# ccnor_stm32_v24-sync-unified-ss.net
KiCad netlist of a schematic drawn in EAGLE
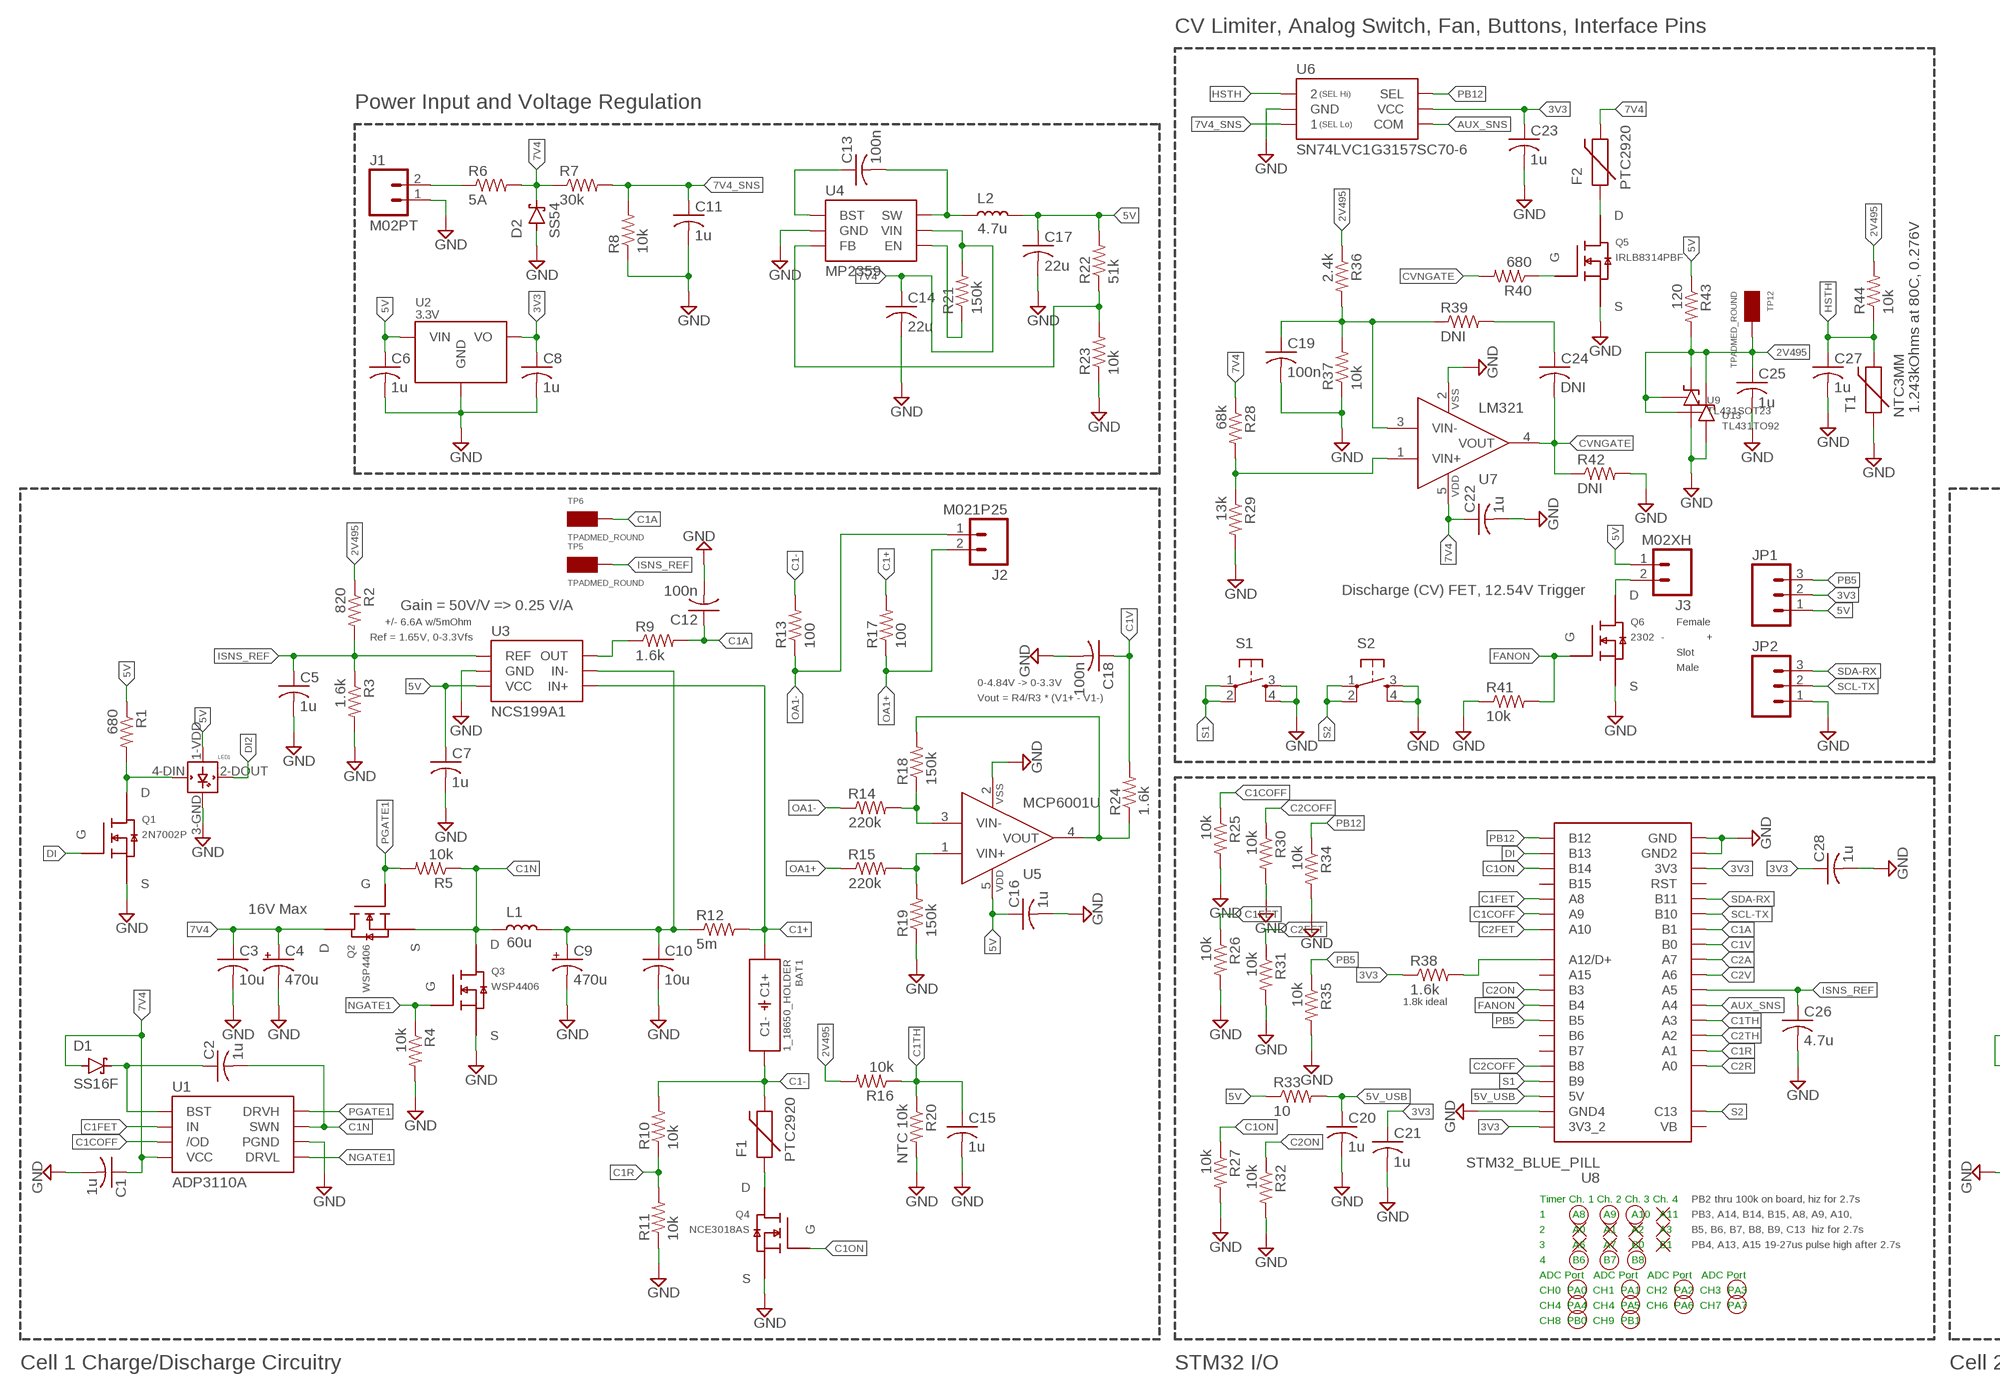
[diagram p0: schematic, sheet 1, part 1 of 2]
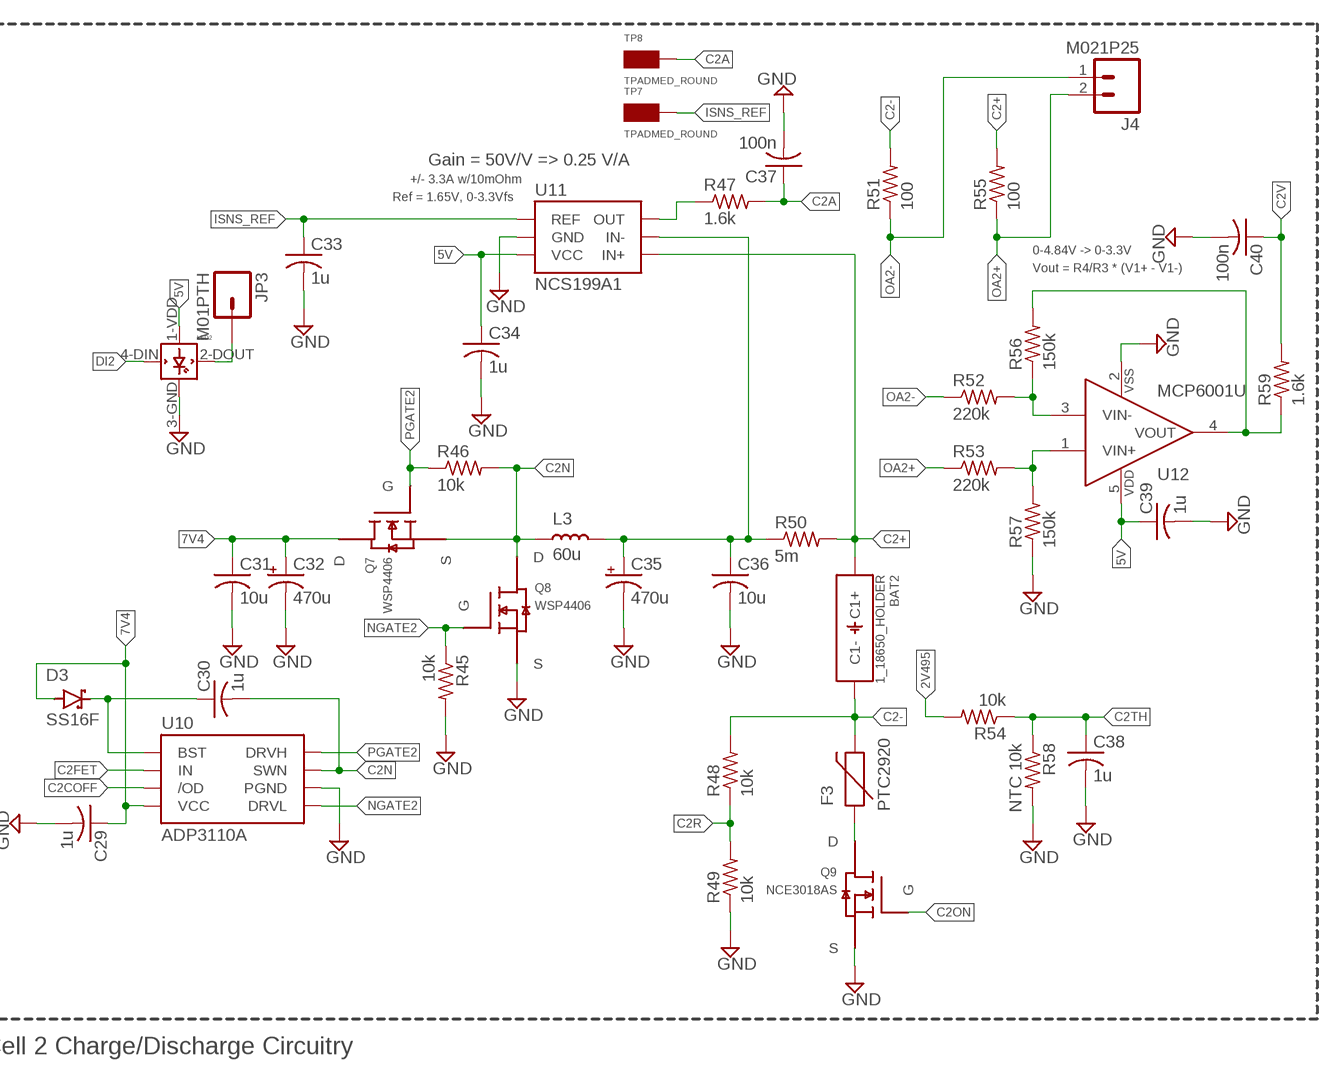
[diagram p1: schematic, sheet 1, part 2 of 2]

(export (version "E")
  (design (tool "Eeschema 10.0.6"))
  (components
    (comp (ref "BAT1")
      (value "1_18650_HOLDER")
      (footprint "eagle-import:1S_18650_SMD_NH")
      (libsource (lib "eagle-import") (part "1_18650_HOLDER"))
    )
    (comp (ref "BAT2")
      (value "1_18650_HOLDER")
      (footprint "eagle-import:1S_18650_SMD_NH")
      (libsource (lib "eagle-import") (part "1_18650_HOLDER"))
    )
    (comp (ref "C1")
      (value "1u")
      (footprint "eagle-import:C0402")
      (libsource (lib "eagle-import") (part "C-USC0402"))
    )
    (comp (ref "C2")
      (value "1u")
      (footprint "eagle-import:C0603")
      (libsource (lib "eagle-import") (part "C-USC0603"))
    )
    (comp (ref "C3")
      (value "10u")
      (footprint "eagle-import:C1206")
      (libsource (lib "eagle-import") (part "C-USC1206"))
    )
    (comp (ref "C4")
      (value "470u")
      (footprint "eagle-import:E2,5-7")
      (libsource (lib "eagle-import") (part "CPOL-USE2.5-7"))
    )
    (comp (ref "C5")
      (value "1u")
      (footprint "eagle-import:C0402")
      (libsource (lib "eagle-import") (part "C-USC0402"))
    )
    (comp (ref "C6")
      (value "1u")
      (footprint "eagle-import:C0402")
      (libsource (lib "eagle-import") (part "C-USC0402"))
    )
    (comp (ref "C7")
      (value "1u")
      (footprint "eagle-import:C0402")
      (libsource (lib "eagle-import") (part "C-USC0402"))
    )
    (comp (ref "C8")
      (value "1u")
      (footprint "eagle-import:C0402")
      (libsource (lib "eagle-import") (part "C-USC0402"))
    )
    (comp (ref "C9")
      (value "470u")
      (footprint "eagle-import:E2,5-7")
      (libsource (lib "eagle-import") (part "CPOL-USE2.5-7"))
    )
    (comp (ref "C10")
      (value "10u")
      (footprint "eagle-import:C1206")
      (libsource (lib "eagle-import") (part "C-USC1206"))
    )
    (comp (ref "C11")
      (value "1u")
      (footprint "eagle-import:C0402")
      (libsource (lib "eagle-import") (part "C-USC0402"))
    )
    (comp (ref "C12")
      (value "100n")
      (footprint "eagle-import:C0402")
      (libsource (lib "eagle-import") (part "C-USC0402"))
    )
    (comp (ref "C13")
      (value "100n")
      (footprint "eagle-import:C0402")
      (libsource (lib "eagle-import") (part "C-USC0402"))
    )
    (comp (ref "C14")
      (value "22u")
      (footprint "eagle-import:C0805")
      (libsource (lib "eagle-import") (part "C-USC0805"))
    )
    (comp (ref "C15")
      (value "1u")
      (footprint "eagle-import:C0402")
      (libsource (lib "eagle-import") (part "C-USC0402"))
    )
    (comp (ref "C16")
      (value "1u")
      (footprint "eagle-import:C0402")
      (libsource (lib "eagle-import") (part "C-USC0402"))
    )
    (comp (ref "C17")
      (value "22u")
      (footprint "eagle-import:C0603")
      (libsource (lib "eagle-import") (part "C-USC0603"))
    )
    (comp (ref "C18")
      (value "100n")
      (footprint "eagle-import:C0402")
      (libsource (lib "eagle-import") (part "C-USC0402"))
    )
    (comp (ref "C19")
      (value "100n")
      (footprint "eagle-import:C0402")
      (libsource (lib "eagle-import") (part "C-USC0402"))
    )
    (comp (ref "C20")
      (value "1u")
      (footprint "eagle-import:C0402")
      (libsource (lib "eagle-import") (part "C-USC0402"))
    )
    (comp (ref "C21")
      (value "1u")
      (footprint "eagle-import:C0402")
      (libsource (lib "eagle-import") (part "C-USC0402"))
    )
    (comp (ref "C22")
      (value "1u")
      (footprint "eagle-import:C0402")
      (libsource (lib "eagle-import") (part "C-USC0402"))
    )
    (comp (ref "C23")
      (value "1u")
      (footprint "eagle-import:C0402")
      (libsource (lib "eagle-import") (part "C-USC0402"))
    )
    (comp (ref "C24")
      (value "DNI")
      (footprint "eagle-import:C0402")
      (libsource (lib "eagle-import") (part "C-USC0402"))
    )
    (comp (ref "C25")
      (value "1u")
      (footprint "eagle-import:C0402")
      (libsource (lib "eagle-import") (part "C-USC0402"))
    )
    (comp (ref "C26")
      (value "4.7u")
      (footprint "eagle-import:C0402")
      (libsource (lib "eagle-import") (part "C-USC0402"))
    )
    (comp (ref "C27")
      (value "1u")
      (footprint "eagle-import:C0402")
      (libsource (lib "eagle-import") (part "C-USC0402"))
    )
    (comp (ref "C28")
      (value "1u")
      (footprint "eagle-import:C0402")
      (libsource (lib "eagle-import") (part "C-USC0402"))
    )
    (comp (ref "C29")
      (value "1u")
      (footprint "eagle-import:C0402")
      (libsource (lib "eagle-import") (part "C-USC0402"))
    )
    (comp (ref "C30")
      (value "1u")
      (footprint "eagle-import:C0603")
      (libsource (lib "eagle-import") (part "C-USC0603"))
    )
    (comp (ref "C31")
      (value "10u")
      (footprint "eagle-import:C1206")
      (libsource (lib "eagle-import") (part "C-USC1206"))
    )
    (comp (ref "C32")
      (value "470u")
      (footprint "eagle-import:E2,5-7")
      (libsource (lib "eagle-import") (part "CPOL-USE2.5-7"))
    )
    (comp (ref "C33")
      (value "1u")
      (footprint "eagle-import:C0402")
      (libsource (lib "eagle-import") (part "C-USC0402"))
    )
    (comp (ref "C34")
      (value "1u")
      (footprint "eagle-import:C0402")
      (libsource (lib "eagle-import") (part "C-USC0402"))
    )
    (comp (ref "C35")
      (value "470u")
      (footprint "eagle-import:E2,5-7")
      (libsource (lib "eagle-import") (part "CPOL-USE2.5-7"))
    )
    (comp (ref "C36")
      (value "10u")
      (footprint "eagle-import:C1206")
      (libsource (lib "eagle-import") (part "C-USC1206"))
    )
    (comp (ref "C37")
      (value "100n")
      (footprint "eagle-import:C0402")
      (libsource (lib "eagle-import") (part "C-USC0402"))
    )
    (comp (ref "C38")
      (value "1u")
      (footprint "eagle-import:C0402")
      (libsource (lib "eagle-import") (part "C-USC0402"))
    )
    (comp (ref "C39")
      (value "1u")
      (footprint "eagle-import:C0402")
      (libsource (lib "eagle-import") (part "C-USC0402"))
    )
    (comp (ref "C40")
      (value "100n")
      (footprint "eagle-import:C0402")
      (libsource (lib "eagle-import") (part "C-USC0402"))
    )
    (comp (ref "D1")
      (value "SS16F")
      (footprint "eagle-import:SOD123")
      (libsource (lib "eagle-import") (part "DIODE_SCHOTTKYCDBM140-G"))
    )
    (comp (ref "D2")
      (value "SS54")
      (footprint "eagle-import:SMA")
      (libsource (lib "eagle-import") (part "SS54"))
    )
    (comp (ref "D3")
      (value "SS16F")
      (footprint "eagle-import:SOD123")
      (libsource (lib "eagle-import") (part "DIODE_SCHOTTKYCDBM140-G"))
    )
    (comp (ref "F1")
      (value "PTC2920")
      (footprint "eagle-import:2920")
      (libsource (lib "eagle-import") (part "PTC2920"))
    )
    (comp (ref "F2")
      (value "PTC2920")
      (footprint "eagle-import:2920")
      (libsource (lib "eagle-import") (part "PTC2920"))
    )
    (comp (ref "F3")
      (value "PTC2920")
      (footprint "eagle-import:2920")
      (libsource (lib "eagle-import") (part "PTC2920"))
    )
    (comp (ref "J1")
      (value "M02PT")
      (footprint "eagle-import:PHOENIXCONTACT1935161")
      (libsource (lib "eagle-import") (part "M02PT"))
    )
    (comp (ref "J2")
      (value "M021P25")
      (footprint "eagle-import:M02_1P25MM")
      (libsource (lib "eagle-import") (part "M021P25"))
    )
    (comp (ref "J3")
      (value "M02XH")
      (footprint "eagle-import:B2B-XH-A")
      (libsource (lib "eagle-import") (part "M02XH"))
    )
    (comp (ref "J4")
      (value "M021P25")
      (footprint "eagle-import:M02_1P25MM")
      (libsource (lib "eagle-import") (part "M021P25"))
    )
    (comp (ref "JP1")
      (value "M03PTH")
      (footprint "eagle-import:1X03")
      (libsource (lib "eagle-import") (part "M03PTH"))
    )
    (comp (ref "JP2")
      (value "M03PTH")
      (footprint "eagle-import:1X03")
      (libsource (lib "eagle-import") (part "M03PTH"))
    )
    (comp (ref "JP3")
      (value "M01PTH")
      (footprint "eagle-import:1X01")
      (libsource (lib "eagle-import") (part "M01PTH"))
    )
    (comp (ref "L1")
      (value "60u")
      (footprint "eagle-import:INDUCTOR_10A_8.2MMX21MM")
      (libsource (lib "eagle-import") (part "INDUCTOR10A"))
    )
    (comp (ref "L2")
      (value "4.7u")
      (footprint "eagle-import:0805")
      (libsource (lib "eagle-import") (part "INDUCTOR0805"))
    )
    (comp (ref "L3")
      (value "60u")
      (footprint "eagle-import:INDUCTOR_10A_8.2MMX21MM")
      (libsource (lib "eagle-import") (part "INDUCTOR10A"))
    )
    (comp (ref "LED1")
      (value "WS2812B")
      (footprint "eagle-import:WS2812B")
      (libsource (lib "eagle-import") (part "WS2812B"))
    )
    (comp (ref "LED2")
      (value "WS2812B")
      (footprint "eagle-import:WS2812B")
      (libsource (lib "eagle-import") (part "WS2812B"))
    )
    (comp (ref "Q1")
      (value "2N7002P")
      (footprint "eagle-import:SOT23")
      (libsource (lib "eagle-import") (part "2N7002P"))
    )
    (comp (ref "Q2")
      (value "WSP4406")
      (footprint "eagle-import:8-SOIC")
      (libsource (lib "eagle-import") (part "N-MOSFET-SOIC8"))
    )
    (comp (ref "Q3")
      (value "WSP4406")
      (footprint "eagle-import:8-SOIC")
      (libsource (lib "eagle-import") (part "N-MOSFET-SOIC8"))
    )
    (comp (ref "Q4")
      (value "NCE3018AS")
      (footprint "eagle-import:8-SOIC")
      (libsource (lib "eagle-import") (part "N-MOSFET-SOIC8"))
    )
    (comp (ref "Q5")
      (value "IRLB8314PBF")
      (footprint "eagle-import:TO-220")
      (libsource (lib "eagle-import") (part "IRLB8314PBF"))
    )
    (comp (ref "Q6")
      (value "2302")
      (footprint "eagle-import:SOT23")
      (libsource (lib "eagle-import") (part "2N7002P"))
    )
    (comp (ref "Q7")
      (value "WSP4406")
      (footprint "eagle-import:8-SOIC")
      (libsource (lib "eagle-import") (part "N-MOSFET-SOIC8"))
    )
    (comp (ref "Q8")
      (value "WSP4406")
      (footprint "eagle-import:8-SOIC")
      (libsource (lib "eagle-import") (part "N-MOSFET-SOIC8"))
    )
    (comp (ref "Q9")
      (value "NCE3018AS")
      (footprint "eagle-import:8-SOIC")
      (libsource (lib "eagle-import") (part "N-MOSFET-SOIC8"))
    )
    (comp (ref "R1")
      (value "680")
      (footprint "eagle-import:R0402")
      (libsource (lib "eagle-import") (part "R-US_R0402"))
    )
    (comp (ref "R2")
      (value "820")
      (footprint "eagle-import:R0402")
      (libsource (lib "eagle-import") (part "R-US_R0402"))
    )
    (comp (ref "R3")
      (value "1.6k")
      (footprint "eagle-import:R0402")
      (libsource (lib "eagle-import") (part "R-US_R0402"))
    )
    (comp (ref "R4")
      (value "10k")
      (footprint "eagle-import:R0402")
      (libsource (lib "eagle-import") (part "R-US_R0402"))
    )
    (comp (ref "R5")
      (value "10k")
      (footprint "eagle-import:R0402")
      (libsource (lib "eagle-import") (part "R-US_R0402"))
    )
    (comp (ref "R6")
      (value "5A")
      (footprint "eagle-import:R1206")
      (libsource (lib "eagle-import") (part "R-US_R1206"))
    )
    (comp (ref "R7")
      (value "30k")
      (footprint "eagle-import:R0402")
      (libsource (lib "eagle-import") (part "R-US_R0402"))
    )
    (comp (ref "R8")
      (value "10k")
      (footprint "eagle-import:R0402")
      (libsource (lib "eagle-import") (part "R-US_R0402"))
    )
    (comp (ref "R9")
      (value "1.6k")
      (footprint "eagle-import:R0402")
      (libsource (lib "eagle-import") (part "R-US_R0402"))
    )
    (comp (ref "R10")
      (value "10k")
      (footprint "eagle-import:R0402")
      (libsource (lib "eagle-import") (part "R-US_R0402"))
    )
    (comp (ref "R11")
      (value "10k")
      (footprint "eagle-import:R0402")
      (libsource (lib "eagle-import") (part "R-US_R0402"))
    )
    (comp (ref "R12")
      (value "5m")
      (footprint "eagle-import:R1206")
      (libsource (lib "eagle-import") (part "R-US_R1206"))
    )
    (comp (ref "R13")
      (value "100")
      (footprint "eagle-import:R0402")
      (libsource (lib "eagle-import") (part "R-US_R0402"))
    )
    (comp (ref "R14")
      (value "220k")
      (footprint "eagle-import:R0402")
      (libsource (lib "eagle-import") (part "R-US_R0402"))
    )
    (comp (ref "R15")
      (value "220k")
      (footprint "eagle-import:R0402")
      (libsource (lib "eagle-import") (part "R-US_R0402"))
    )
    (comp (ref "R16")
      (value "10k")
      (footprint "eagle-import:R0402")
      (libsource (lib "eagle-import") (part "R-US_R0402"))
    )
    (comp (ref "R17")
      (value "100")
      (footprint "eagle-import:R0402")
      (libsource (lib "eagle-import") (part "R-US_R0402"))
    )
    (comp (ref "R18")
      (value "150k")
      (footprint "eagle-import:R0402")
      (libsource (lib "eagle-import") (part "R-US_R0402"))
    )
    (comp (ref "R19")
      (value "150k")
      (footprint "eagle-import:R0402")
      (libsource (lib "eagle-import") (part "R-US_R0402"))
    )
    (comp (ref "R20")
      (value "NTC 10k")
      (footprint "eagle-import:R0402")
      (libsource (lib "eagle-import") (part "R-US_R0402"))
    )
    (comp (ref "R21")
      (value "150k")
      (footprint "eagle-import:R0402")
      (libsource (lib "eagle-import") (part "R-US_R0402"))
    )
    (comp (ref "R22")
      (value "51k")
      (footprint "eagle-import:R0402")
      (libsource (lib "eagle-import") (part "R-US_R0402"))
    )
    (comp (ref "R23")
      (value "10k")
      (footprint "eagle-import:R0402")
      (libsource (lib "eagle-import") (part "R-US_R0402"))
    )
    (comp (ref "R24")
      (value "1.6k")
      (footprint "eagle-import:R0402")
      (libsource (lib "eagle-import") (part "R-US_R0402"))
    )
    (comp (ref "R25")
      (value "10k")
      (footprint "eagle-import:R0402")
      (libsource (lib "eagle-import") (part "R-US_R0402"))
    )
    (comp (ref "R26")
      (value "10k")
      (footprint "eagle-import:R0402")
      (libsource (lib "eagle-import") (part "R-US_R0402"))
    )
    (comp (ref "R27")
      (value "10k")
      (footprint "eagle-import:R0402")
      (libsource (lib "eagle-import") (part "R-US_R0402"))
    )
    (comp (ref "R28")
      (value "68k")
      (footprint "eagle-import:R0402")
      (libsource (lib "eagle-import") (part "R-US_R0402"))
    )
    (comp (ref "R29")
      (value "13k")
      (footprint "eagle-import:R0402")
      (libsource (lib "eagle-import") (part "R-US_R0402"))
    )
    (comp (ref "R30")
      (value "10k")
      (footprint "eagle-import:R0402")
      (libsource (lib "eagle-import") (part "R-US_R0402"))
    )
    (comp (ref "R31")
      (value "10k")
      (footprint "eagle-import:R0402")
      (libsource (lib "eagle-import") (part "R-US_R0402"))
    )
    (comp (ref "R32")
      (value "10k")
      (footprint "eagle-import:R0402")
      (libsource (lib "eagle-import") (part "R-US_R0402"))
    )
    (comp (ref "R33")
      (value "10")
      (footprint "eagle-import:R0402")
      (libsource (lib "eagle-import") (part "R-US_R0402"))
    )
    (comp (ref "R34")
      (value "10k")
      (footprint "eagle-import:R0402")
      (libsource (lib "eagle-import") (part "R-US_R0402"))
    )
    (comp (ref "R35")
      (value "10k")
      (footprint "eagle-import:R0402")
      (libsource (lib "eagle-import") (part "R-US_R0402"))
    )
    (comp (ref "R36")
      (value "2.4k")
      (footprint "eagle-import:R0402")
      (libsource (lib "eagle-import") (part "R-US_R0402"))
    )
    (comp (ref "R37")
      (value "10k")
      (footprint "eagle-import:R0402")
      (libsource (lib "eagle-import") (part "R-US_R0402"))
    )
    (comp (ref "R38")
      (value "1.6k")
      (footprint "eagle-import:R0402")
      (libsource (lib "eagle-import") (part "R-US_R0402"))
    )
    (comp (ref "R39")
      (value "DNI")
      (footprint "eagle-import:R0402")
      (libsource (lib "eagle-import") (part "R-US_R0402"))
    )
    (comp (ref "R40")
      (value "680")
      (footprint "eagle-import:R0402")
      (libsource (lib "eagle-import") (part "R-US_R0402"))
    )
    (comp (ref "R41")
      (value "10k")
      (footprint "eagle-import:R0402")
      (libsource (lib "eagle-import") (part "R-US_R0402"))
    )
    (comp (ref "R42")
      (value "DNI")
      (footprint "eagle-import:R0402")
      (libsource (lib "eagle-import") (part "R-US_R0402"))
    )
    (comp (ref "R43")
      (value "120")
      (footprint "eagle-import:R0402")
      (libsource (lib "eagle-import") (part "R-US_R0402"))
    )
    (comp (ref "R44")
      (value "10k")
      (footprint "eagle-import:R0402")
      (libsource (lib "eagle-import") (part "R-US_R0402"))
    )
    (comp (ref "R45")
      (value "10k")
      (footprint "eagle-import:R0402")
      (libsource (lib "eagle-import") (part "R-US_R0402"))
    )
    (comp (ref "R46")
      (value "10k")
      (footprint "eagle-import:R0402")
      (libsource (lib "eagle-import") (part "R-US_R0402"))
    )
    (comp (ref "R47")
      (value "1.6k")
      (footprint "eagle-import:R0402")
      (libsource (lib "eagle-import") (part "R-US_R0402"))
    )
    (comp (ref "R48")
      (value "10k")
      (footprint "eagle-import:R0402")
      (libsource (lib "eagle-import") (part "R-US_R0402"))
    )
    (comp (ref "R49")
      (value "10k")
      (footprint "eagle-import:R0402")
      (libsource (lib "eagle-import") (part "R-US_R0402"))
    )
    (comp (ref "R50")
      (value "5m")
      (footprint "eagle-import:R1206")
      (libsource (lib "eagle-import") (part "R-US_R1206"))
    )
    (comp (ref "R51")
      (value "100")
      (footprint "eagle-import:R0402")
      (libsource (lib "eagle-import") (part "R-US_R0402"))
    )
    (comp (ref "R52")
      (value "220k")
      (footprint "eagle-import:R0402")
      (libsource (lib "eagle-import") (part "R-US_R0402"))
    )
    (comp (ref "R53")
      (value "220k")
      (footprint "eagle-import:R0402")
      (libsource (lib "eagle-import") (part "R-US_R0402"))
    )
    (comp (ref "R54")
      (value "10k")
      (footprint "eagle-import:R0402")
      (libsource (lib "eagle-import") (part "R-US_R0402"))
    )
    (comp (ref "R55")
      (value "100")
      (footprint "eagle-import:R0402")
      (libsource (lib "eagle-import") (part "R-US_R0402"))
    )
    (comp (ref "R56")
      (value "150k")
      (footprint "eagle-import:R0402")
      (libsource (lib "eagle-import") (part "R-US_R0402"))
    )
    (comp (ref "R57")
      (value "150k")
      (footprint "eagle-import:R0402")
      (libsource (lib "eagle-import") (part "R-US_R0402"))
    )
    (comp (ref "R58")
      (value "NTC 10k")
      (footprint "eagle-import:R0402")
      (libsource (lib "eagle-import") (part "R-US_R0402"))
    )
    (comp (ref "R59")
      (value "1.6k")
      (footprint "eagle-import:R0402")
      (libsource (lib "eagle-import") (part "R-US_R0402"))
    )
    (comp (ref "S1")
      (value "TAC_SWITCHSMD")
      (footprint "eagle-import:TACTILE_SWITCH_SMD")
      (libsource (lib "eagle-import") (part "TAC_SWITCHSMD"))
    )
    (comp (ref "S2")
      (value "TAC_SWITCHSMD")
      (footprint "eagle-import:TACTILE_SWITCH_SMD")
      (libsource (lib "eagle-import") (part "TAC_SWITCHSMD"))
    )
    (comp (ref "T1")
      (value "NTC3MM")
      (footprint "eagle-import:THERMISTOR_3MMX3MM")
      (libsource (lib "eagle-import") (part "PTCNTC3MM"))
    )
    (comp (ref "TP5")
      (value "TPADMED_ROUND")
      (footprint "eagle-import:TPAD_MED_ROUND")
      (libsource (lib "eagle-import") (part "TPADMED_ROUND"))
    )
    (comp (ref "TP6")
      (value "TPADMED_ROUND")
      (footprint "eagle-import:TPAD_MED_ROUND")
      (libsource (lib "eagle-import") (part "TPADMED_ROUND"))
    )
    (comp (ref "TP7")
      (value "TPADMED_ROUND")
      (footprint "eagle-import:TPAD_MED_ROUND")
      (libsource (lib "eagle-import") (part "TPADMED_ROUND"))
    )
    (comp (ref "TP8")
      (value "TPADMED_ROUND")
      (footprint "eagle-import:TPAD_MED_ROUND")
      (libsource (lib "eagle-import") (part "TPADMED_ROUND"))
    )
    (comp (ref "TP12")
      (value "TPADMED_ROUND")
      (footprint "eagle-import:TPAD_MED_ROUND")
      (libsource (lib "eagle-import") (part "TPADMED_ROUND"))
    )
    (comp (ref "U1")
      (value "ADP3110A")
      (footprint "eagle-import:8-SOIC")
      (libsource (lib "eagle-import") (part "ADP3110A"))
    )
    (comp (ref "U2")
      (value "3.3V")
      (footprint "eagle-import:SOT-89")
      (libsource (lib "eagle-import") (part "AP1117UR133-B"))
    )
    (comp (ref "U3")
      (value "NCS199A1")
      (footprint "eagle-import:SOT-363")
      (libsource (lib "eagle-import") (part "INA214"))
    )
    (comp (ref "U4")
      (value "MP2359")
      (footprint "eagle-import:SOT23-6")
      (libsource (lib "eagle-import") (part "JW5052C"))
    )
    (comp (ref "U5")
      (value "MCP6001U")
      (footprint "eagle-import:SOT23-5")
      (libsource (lib "eagle-import") (part "MCP6001U"))
    )
    (comp (ref "U6")
      (value "SN74LVC1G3157SC70-6")
      (footprint "eagle-import:SC70-6")
      (libsource (lib "eagle-import") (part "SN74LVC1G3157SC70-6"))
    )
    (comp (ref "U7")
      (value "LM321")
      (footprint "eagle-import:SOT23-5")
      (libsource (lib "eagle-import") (part "LM321"))
    )
    (comp (ref "U8")
      (value "STM32_BLUE_PILL")
      (footprint "eagle-import:STM32_BLUE_PILL_USABLE")
      (libsource (lib "eagle-import") (part "STM32_BLUE_PILL"))
    )
    (comp (ref "U9")
      (value "TL431SOT23")
      (footprint "eagle-import:SOT23")
      (libsource (lib "eagle-import") (part "TL431SOT23"))
    )
    (comp (ref "U10")
      (value "ADP3110A")
      (footprint "eagle-import:8-SOIC")
      (libsource (lib "eagle-import") (part "ADP3110A"))
    )
    (comp (ref "U11")
      (value "NCS199A1")
      (footprint "eagle-import:SOT-363")
      (libsource (lib "eagle-import") (part "INA214"))
    )
    (comp (ref "U12")
      (value "MCP6001U")
      (footprint "eagle-import:SOT23-5")
      (libsource (lib "eagle-import") (part "MCP6001U"))
    )
    (comp (ref "U13")
      (value "TL431TO92")
      (footprint "eagle-import:TO-92")
      (libsource (lib "eagle-import") (part "TL431TO92"))
    )
  )
  (nets
    (net (code "1") (name "2V495") (class "Default")
      (node (ref "C25") (pin "1") (pinfunction "1_1") (pintype "passive"))
      (node (ref "R16") (pin "2") (pinfunction "2_2") (pintype "passive"))
      (node (ref "R2") (pin "1") (pinfunction "1_1") (pintype "passive"))
      (node (ref "R36") (pin "1") (pinfunction "1_1") (pintype "passive"))
      (node (ref "R43") (pin "2") (pinfunction "2_2") (pintype "passive"))
      (node (ref "R44") (pin "2") (pinfunction "2_2") (pintype "passive"))
      (node (ref "R54") (pin "2") (pinfunction "2_2") (pintype "passive"))
      (node (ref "TP12") (pin "1") (pinfunction "1_1") (pintype "bidirectional"))
      (node (ref "U13") (pin "1") (pinfunction "REF_1") (pintype "passive"))
      (node (ref "U13") (pin "3") (pinfunction "K_3") (pintype "passive"))
      (node (ref "U9") (pin "1") (pinfunction "K_1") (pintype "passive"))
      (node (ref "U9") (pin "2") (pinfunction "REF_2") (pintype "passive"))
    )
    (net (code "2") (name "3V3") (class "Default")
      (node (ref "C21") (pin "1") (pinfunction "1_1") (pintype "passive"))
      (node (ref "C23") (pin "1") (pinfunction "1_1") (pintype "passive"))
      (node (ref "C28") (pin "1") (pinfunction "1_1") (pintype "passive"))
      (node (ref "C8") (pin "1") (pinfunction "1_1") (pintype "passive"))
      (node (ref "JP1") (pin "2") (pinfunction "2_2") (pintype "passive"))
      (node (ref "R38") (pin "1") (pinfunction "1_1") (pintype "passive"))
      (node (ref "U2") (pin "1") (pinfunction "VO_1") (pintype "bidirectional"))
      (node (ref "U6") (pin "5") (pinfunction "VCC_5") (pintype "bidirectional"))
      (node (ref "U8") (pin "3V3") (pinfunction "3V3_3V3") (pintype "bidirectional"))
      (node (ref "U8") (pin "3V3_2") (pinfunction "3V3_2_3V3_2") (pintype "bidirectional"))
    )
    (net (code "3") (name "5V") (class "Default")
      (node (ref "C16") (pin "1") (pinfunction "1_1") (pintype "passive"))
      (node (ref "C17") (pin "1") (pinfunction "1_1") (pintype "passive"))
      (node (ref "C34") (pin "1") (pinfunction "1_1") (pintype "passive"))
      (node (ref "C39") (pin "1") (pinfunction "1_1") (pintype "passive"))
      (node (ref "C6") (pin "1") (pinfunction "1_1") (pintype "passive"))
      (node (ref "C7") (pin "1") (pinfunction "1_1") (pintype "passive"))
      (node (ref "J3") (pin "1") (pinfunction "1_1") (pintype "passive"))
      (node (ref "JP1") (pin "1") (pinfunction "1_1") (pintype "passive"))
      (node (ref "L2") (pin "2") (pinfunction "P$2_2") (pintype "passive"))
      (node (ref "LED1") (pin "1-VDD") (pinfunction "VDD_1-VDD") (pintype "bidirectional"))
      (node (ref "LED2") (pin "1-VDD") (pinfunction "VDD_1-VDD") (pintype "bidirectional"))
      (node (ref "R1") (pin "1") (pinfunction "1_1") (pintype "passive"))
      (node (ref "R22") (pin "2") (pinfunction "2_2") (pintype "passive"))
      (node (ref "R33") (pin "1") (pinfunction "1_1") (pintype "passive"))
      (node (ref "R43") (pin "1") (pinfunction "1_1") (pintype "passive"))
      (node (ref "U11") (pin "3") (pinfunction "VCC_3") (pintype "bidirectional"))
      (node (ref "U12") (pin "5") (pinfunction "VDD_5") (pintype "bidirectional"))
      (node (ref "U2") (pin "3") (pinfunction "VIN_3") (pintype "bidirectional"))
      (node (ref "U3") (pin "3") (pinfunction "VCC_3") (pintype "bidirectional"))
      (node (ref "U5") (pin "5") (pinfunction "VDD_5") (pintype "bidirectional"))
    )
    (net (code "4") (name "5V_USB") (class "Default")
      (node (ref "C20") (pin "1") (pinfunction "1_1") (pintype "passive"))
      (node (ref "R33") (pin "2") (pinfunction "2_2") (pintype "passive"))
      (node (ref "U8") (pin "5V") (pinfunction "5V_5V") (pintype "bidirectional"))
    )
    (net (code "5") (name "7V4") (class "Default")
      (node (ref "C1") (pin "1") (pinfunction "1_1") (pintype "passive"))
      (node (ref "C14") (pin "1") (pinfunction "1_1") (pintype "passive"))
      (node (ref "C22") (pin "1") (pinfunction "1_1") (pintype "passive"))
      (node (ref "C29") (pin "1") (pinfunction "1_1") (pintype "passive"))
      (node (ref "C3") (pin "1") (pinfunction "1_1") (pintype "passive"))
      (node (ref "C31") (pin "1") (pinfunction "1_1") (pintype "passive"))
      (node (ref "C32") (pin "+") (pinfunction "+_+") (pintype "passive"))
      (node (ref "C4") (pin "+") (pinfunction "+_+") (pintype "passive"))
      (node (ref "D1") (pin "A") (pinfunction "ANODE_A") (pintype "passive"))
      (node (ref "D2") (pin "K") (pinfunction "CATHODE_K") (pintype "passive"))
      (node (ref "D3") (pin "A") (pinfunction "ANODE_A") (pintype "passive"))
      (node (ref "F2") (pin "K") (pinfunction "2_K") (pintype "bidirectional"))
      (node (ref "Q2") (pin "5") (pinfunction "D_5") (pintype "bidirectional"))
      (node (ref "Q2") (pin "6") (pinfunction "D_6") (pintype "bidirectional"))
      (node (ref "Q2") (pin "7") (pinfunction "D_7") (pintype "bidirectional"))
      (node (ref "Q2") (pin "8") (pinfunction "D_8") (pintype "bidirectional"))
      (node (ref "Q7") (pin "5") (pinfunction "D_5") (pintype "bidirectional"))
      (node (ref "Q7") (pin "6") (pinfunction "D_6") (pintype "bidirectional"))
      (node (ref "Q7") (pin "7") (pinfunction "D_7") (pintype "bidirectional"))
      (node (ref "Q7") (pin "8") (pinfunction "D_8") (pintype "bidirectional"))
      (node (ref "R21") (pin "2") (pinfunction "2_2") (pintype "passive"))
      (node (ref "R28") (pin "1") (pinfunction "1_1") (pintype "passive"))
      (node (ref "R6") (pin "2") (pinfunction "2_2") (pintype "passive"))
      (node (ref "R7") (pin "1") (pinfunction "1_1") (pintype "passive"))
      (node (ref "U1") (pin "4") (pinfunction "VCC_4") (pintype "bidirectional"))
      (node (ref "U10") (pin "4") (pinfunction "VCC_4") (pintype "bidirectional"))
      (node (ref "U4") (pin "5") (pinfunction "VIN_5") (pintype "bidirectional"))
      (node (ref "U7") (pin "5") (pinfunction "VDD_5") (pintype "bidirectional"))
    )
    (net (code "6") (name "7V4_SNS") (class "Default")
      (node (ref "C11") (pin "1") (pinfunction "1_1") (pintype "passive"))
      (node (ref "R7") (pin "2") (pinfunction "2_2") (pintype "passive"))
      (node (ref "R8") (pin "2") (pinfunction "2_2") (pintype "passive"))
      (node (ref "U6") (pin "3") (pinfunction "1_3") (pintype "bidirectional"))
    )
    (net (code "7") (name "AUX_SNS") (class "Default")
      (node (ref "U6") (pin "4") (pinfunction "COM_4") (pintype "bidirectional"))
      (node (ref "U8") (pin "A4") (pinfunction "A4_A4") (pintype "bidirectional"))
    )
    (net (code "8") (name "C1+") (class "Default")
      (node (ref "BAT1") (pin "1+") (pinfunction "C1+_1+") (pintype "bidirectional"))
      (node (ref "R12") (pin "2") (pinfunction "2_2") (pintype "passive"))
      (node (ref "R17") (pin "2") (pinfunction "2_2") (pintype "passive"))
      (node (ref "U3") (pin "4") (pinfunction "IN+_4") (pintype "bidirectional"))
    )
    (net (code "9") (name "C1-") (class "Default")
      (node (ref "BAT1") (pin "1-") (pinfunction "C1-_1-") (pintype "bidirectional"))
      (node (ref "F1") (pin "K") (pinfunction "2_K") (pintype "bidirectional"))
      (node (ref "R10") (pin "2") (pinfunction "2_2") (pintype "passive"))
      (node (ref "R13") (pin "2") (pinfunction "2_2") (pintype "passive"))
    )
    (net (code "10") (name "C1A") (class "Default")
      (node (ref "C12") (pin "1") (pinfunction "1_1") (pintype "passive"))
      (node (ref "R9") (pin "2") (pinfunction "2_2") (pintype "passive"))
      (node (ref "TP6") (pin "1") (pinfunction "1_1") (pintype "bidirectional"))
      (node (ref "U8") (pin "B1") (pinfunction "B1_B1") (pintype "bidirectional"))
    )
    (net (code "11") (name "C1COFF") (class "Default")
      (node (ref "R25") (pin "1") (pinfunction "1_1") (pintype "passive"))
      (node (ref "U1") (pin "3") (pinfunction "/OD_3") (pintype "bidirectional"))
      (node (ref "U8") (pin "A9") (pinfunction "A9_A9") (pintype "bidirectional"))
    )
    (net (code "12") (name "C1FET") (class "Default")
      (node (ref "R26") (pin "1") (pinfunction "1_1") (pintype "passive"))
      (node (ref "U1") (pin "2") (pinfunction "IN_2") (pintype "bidirectional"))
      (node (ref "U8") (pin "A8") (pinfunction "A8_A8") (pintype "bidirectional"))
    )
    (net (code "13") (name "C1N") (class "Default")
      (node (ref "C2") (pin "2") (pinfunction "2_2") (pintype "passive"))
      (node (ref "L1") (pin "P$1") (pinfunction "P$1_P$1") (pintype "passive"))
      (node (ref "Q2") (pin "1") (pinfunction "S_1") (pintype "bidirectional"))
      (node (ref "Q2") (pin "2") (pinfunction "S_2") (pintype "bidirectional"))
      (node (ref "Q2") (pin "3") (pinfunction "S_3") (pintype "bidirectional"))
      (node (ref "Q3") (pin "5") (pinfunction "D_5") (pintype "bidirectional"))
      (node (ref "Q3") (pin "6") (pinfunction "D_6") (pintype "bidirectional"))
      (node (ref "Q3") (pin "7") (pinfunction "D_7") (pintype "bidirectional"))
      (node (ref "Q3") (pin "8") (pinfunction "D_8") (pintype "bidirectional"))
      (node (ref "R5") (pin "1") (pinfunction "1_1") (pintype "passive"))
      (node (ref "U1") (pin "7") (pinfunction "SWN_7") (pintype "bidirectional"))
    )
    (net (code "14") (name "C1ON") (class "Default")
      (node (ref "Q4") (pin "4") (pinfunction "G_4") (pintype "bidirectional"))
      (node (ref "R27") (pin "1") (pinfunction "1_1") (pintype "passive"))
      (node (ref "U8") (pin "B14") (pinfunction "B14_B14") (pintype "bidirectional"))
    )
    (net (code "15") (name "C1R") (class "Default")
      (node (ref "R10") (pin "1") (pinfunction "1_1") (pintype "passive"))
      (node (ref "R11") (pin "2") (pinfunction "2_2") (pintype "passive"))
      (node (ref "U8") (pin "A1") (pinfunction "A1_A1") (pintype "bidirectional"))
    )
    (net (code "16") (name "C1TH") (class "Default")
      (node (ref "C15") (pin "1") (pinfunction "1_1") (pintype "passive"))
      (node (ref "R16") (pin "1") (pinfunction "1_1") (pintype "passive"))
      (node (ref "R20") (pin "1") (pinfunction "1_1") (pintype "passive"))
      (node (ref "U8") (pin "A3") (pinfunction "A3_A3") (pintype "bidirectional"))
    )
    (net (code "17") (name "C1V") (class "Default")
      (node (ref "C18") (pin "1") (pinfunction "1_1") (pintype "passive"))
      (node (ref "R24") (pin "2") (pinfunction "2_2") (pintype "passive"))
      (node (ref "U8") (pin "B0") (pinfunction "B0_B0") (pintype "bidirectional"))
    )
    (net (code "18") (name "C2+") (class "Default")
      (node (ref "BAT2") (pin "1+") (pinfunction "C1+_1+") (pintype "bidirectional"))
      (node (ref "R50") (pin "2") (pinfunction "2_2") (pintype "passive"))
      (node (ref "R55") (pin "2") (pinfunction "2_2") (pintype "passive"))
      (node (ref "U11") (pin "4") (pinfunction "IN+_4") (pintype "bidirectional"))
    )
    (net (code "19") (name "C2-") (class "Default")
      (node (ref "BAT2") (pin "1-") (pinfunction "C1-_1-") (pintype "bidirectional"))
      (node (ref "F3") (pin "K") (pinfunction "2_K") (pintype "bidirectional"))
      (node (ref "R48") (pin "2") (pinfunction "2_2") (pintype "passive"))
      (node (ref "R51") (pin "2") (pinfunction "2_2") (pintype "passive"))
    )
    (net (code "20") (name "C2A") (class "Default")
      (node (ref "C37") (pin "1") (pinfunction "1_1") (pintype "passive"))
      (node (ref "R47") (pin "2") (pinfunction "2_2") (pintype "passive"))
      (node (ref "TP8") (pin "1") (pinfunction "1_1") (pintype "bidirectional"))
      (node (ref "U8") (pin "A7") (pinfunction "A7_A7") (pintype "bidirectional"))
    )
    (net (code "21") (name "C2COFF") (class "Default")
      (node (ref "R30") (pin "1") (pinfunction "1_1") (pintype "passive"))
      (node (ref "U10") (pin "3") (pinfunction "/OD_3") (pintype "bidirectional"))
      (node (ref "U8") (pin "B8") (pinfunction "B8_B8") (pintype "bidirectional"))
    )
    (net (code "22") (name "C2FET") (class "Default")
      (node (ref "R31") (pin "1") (pinfunction "1_1") (pintype "passive"))
      (node (ref "U10") (pin "2") (pinfunction "IN_2") (pintype "bidirectional"))
      (node (ref "U8") (pin "A10") (pinfunction "A10_A10") (pintype "bidirectional"))
    )
    (net (code "23") (name "C2N") (class "Default")
      (node (ref "C30") (pin "2") (pinfunction "2_2") (pintype "passive"))
      (node (ref "L3") (pin "P$1") (pinfunction "P$1_P$1") (pintype "passive"))
      (node (ref "Q7") (pin "1") (pinfunction "S_1") (pintype "bidirectional"))
      (node (ref "Q7") (pin "2") (pinfunction "S_2") (pintype "bidirectional"))
      (node (ref "Q7") (pin "3") (pinfunction "S_3") (pintype "bidirectional"))
      (node (ref "Q8") (pin "5") (pinfunction "D_5") (pintype "bidirectional"))
      (node (ref "Q8") (pin "6") (pinfunction "D_6") (pintype "bidirectional"))
      (node (ref "Q8") (pin "7") (pinfunction "D_7") (pintype "bidirectional"))
      (node (ref "Q8") (pin "8") (pinfunction "D_8") (pintype "bidirectional"))
      (node (ref "R46") (pin "2") (pinfunction "2_2") (pintype "passive"))
      (node (ref "U10") (pin "7") (pinfunction "SWN_7") (pintype "bidirectional"))
    )
    (net (code "24") (name "C2ON") (class "Default")
      (node (ref "Q9") (pin "4") (pinfunction "G_4") (pintype "bidirectional"))
      (node (ref "R32") (pin "1") (pinfunction "1_1") (pintype "passive"))
      (node (ref "U8") (pin "B3") (pinfunction "B3_B3") (pintype "bidirectional"))
    )
    (net (code "25") (name "C2R") (class "Default")
      (node (ref "R48") (pin "1") (pinfunction "1_1") (pintype "passive"))
      (node (ref "R49") (pin "2") (pinfunction "2_2") (pintype "passive"))
      (node (ref "U8") (pin "A0") (pinfunction "A0_A0") (pintype "bidirectional"))
    )
    (net (code "26") (name "C2TH") (class "Default")
      (node (ref "C38") (pin "1") (pinfunction "1_1") (pintype "passive"))
      (node (ref "R54") (pin "1") (pinfunction "1_1") (pintype "passive"))
      (node (ref "R58") (pin "1") (pinfunction "1_1") (pintype "passive"))
      (node (ref "U8") (pin "A2") (pinfunction "A2_A2") (pintype "bidirectional"))
    )
    (net (code "27") (name "C2V") (class "Default")
      (node (ref "C40") (pin "1") (pinfunction "1_1") (pintype "passive"))
      (node (ref "R59") (pin "2") (pinfunction "2_2") (pintype "passive"))
      (node (ref "U8") (pin "A6") (pinfunction "A6_A6") (pintype "bidirectional"))
    )
    (net (code "28") (name "CVNGATE") (class "Default")
      (node (ref "C24") (pin "2") (pinfunction "2_2") (pintype "passive"))
      (node (ref "R40") (pin "2") (pinfunction "2_2") (pintype "passive"))
      (node (ref "R42") (pin "1") (pinfunction "1_1") (pintype "passive"))
      (node (ref "U7") (pin "4") (pinfunction "VOUT_4") (pintype "bidirectional"))
    )
    (net (code "29") (name "DI") (class "Default")
      (node (ref "Q1") (pin "1") (pinfunction "G_1") (pintype "bidirectional"))
      (node (ref "U8") (pin "B13") (pinfunction "B13_B13") (pintype "bidirectional"))
    )
    (net (code "30") (name "DI2") (class "Default")
      (node (ref "LED1") (pin "2-DOUT") (pinfunction "DOUT_2-DOUT") (pintype "output"))
      (node (ref "LED2") (pin "4-DIN") (pinfunction "DIN_4-DIN") (pintype "input"))
    )
    (net (code "31") (name "FANON") (class "Default")
      (node (ref "Q6") (pin "1") (pinfunction "G_1") (pintype "bidirectional"))
      (node (ref "R41") (pin "2") (pinfunction "2_2") (pintype "passive"))
      (node (ref "U8") (pin "B4") (pinfunction "B4_B4") (pintype "bidirectional"))
    )
    (net (code "32") (name "GND") (class "Default")
      (node (ref "C1") (pin "2") (pinfunction "2_2") (pintype "passive"))
      (node (ref "C10") (pin "2") (pinfunction "2_2") (pintype "passive"))
      (node (ref "C11") (pin "2") (pinfunction "2_2") (pintype "passive"))
      (node (ref "C12") (pin "2") (pinfunction "2_2") (pintype "passive"))
      (node (ref "C14") (pin "2") (pinfunction "2_2") (pintype "passive"))
      (node (ref "C15") (pin "2") (pinfunction "2_2") (pintype "passive"))
      (node (ref "C16") (pin "2") (pinfunction "2_2") (pintype "passive"))
      (node (ref "C17") (pin "2") (pinfunction "2_2") (pintype "passive"))
      (node (ref "C18") (pin "2") (pinfunction "2_2") (pintype "passive"))
      (node (ref "C19") (pin "2") (pinfunction "2_2") (pintype "passive"))
      (node (ref "C20") (pin "2") (pinfunction "2_2") (pintype "passive"))
      (node (ref "C21") (pin "2") (pinfunction "2_2") (pintype "passive"))
      (node (ref "C22") (pin "2") (pinfunction "2_2") (pintype "passive"))
      (node (ref "C23") (pin "2") (pinfunction "2_2") (pintype "passive"))
      (node (ref "C25") (pin "2") (pinfunction "2_2") (pintype "passive"))
      (node (ref "C26") (pin "2") (pinfunction "2_2") (pintype "passive"))
      (node (ref "C27") (pin "2") (pinfunction "2_2") (pintype "passive"))
      (node (ref "C28") (pin "2") (pinfunction "2_2") (pintype "passive"))
      (node (ref "C29") (pin "2") (pinfunction "2_2") (pintype "passive"))
      (node (ref "C3") (pin "2") (pinfunction "2_2") (pintype "passive"))
      (node (ref "C31") (pin "2") (pinfunction "2_2") (pintype "passive"))
      (node (ref "C32") (pin "-") (pinfunction "-_-") (pintype "passive"))
      (node (ref "C33") (pin "2") (pinfunction "2_2") (pintype "passive"))
      (node (ref "C34") (pin "2") (pinfunction "2_2") (pintype "passive"))
      (node (ref "C35") (pin "-") (pinfunction "-_-") (pintype "passive"))
      (node (ref "C36") (pin "2") (pinfunction "2_2") (pintype "passive"))
      (node (ref "C37") (pin "2") (pinfunction "2_2") (pintype "passive"))
      (node (ref "C38") (pin "2") (pinfunction "2_2") (pintype "passive"))
      (node (ref "C39") (pin "2") (pinfunction "2_2") (pintype "passive"))
      (node (ref "C4") (pin "-") (pinfunction "-_-") (pintype "passive"))
      (node (ref "C40") (pin "2") (pinfunction "2_2") (pintype "passive"))
      (node (ref "C5") (pin "2") (pinfunction "2_2") (pintype "passive"))
      (node (ref "C6") (pin "2") (pinfunction "2_2") (pintype "passive"))
      (node (ref "C7") (pin "2") (pinfunction "2_2") (pintype "passive"))
      (node (ref "C8") (pin "2") (pinfunction "2_2") (pintype "passive"))
      (node (ref "C9") (pin "-") (pinfunction "-_-") (pintype "passive"))
      (node (ref "D2") (pin "A") (pinfunction "ANODE_A") (pintype "passive"))
      (node (ref "J1") (pin "1") (pinfunction "1_1") (pintype "passive"))
      (node (ref "JP2") (pin "1") (pinfunction "1_1") (pintype "passive"))
      (node (ref "LED1") (pin "3-GND") (pinfunction "GND_3-GND") (pintype "bidirectional"))
      (node (ref "LED2") (pin "3-GND") (pinfunction "GND_3-GND") (pintype "bidirectional"))
      (node (ref "Q1") (pin "2") (pinfunction "S_2") (pintype "bidirectional"))
      (node (ref "Q3") (pin "1") (pinfunction "S_1") (pintype "bidirectional"))
      (node (ref "Q3") (pin "2") (pinfunction "S_2") (pintype "bidirectional"))
      (node (ref "Q3") (pin "3") (pinfunction "S_3") (pintype "bidirectional"))
      (node (ref "Q4") (pin "1") (pinfunction "S_1") (pintype "bidirectional"))
      (node (ref "Q4") (pin "2") (pinfunction "S_2") (pintype "bidirectional"))
      (node (ref "Q4") (pin "3") (pinfunction "S_3") (pintype "bidirectional"))
      (node (ref "Q5") (pin "3") (pinfunction "S_3") (pintype "bidirectional"))
      (node (ref "Q6") (pin "2") (pinfunction "S_2") (pintype "bidirectional"))
      (node (ref "Q8") (pin "1") (pinfunction "S_1") (pintype "bidirectional"))
      (node (ref "Q8") (pin "2") (pinfunction "S_2") (pintype "bidirectional"))
      (node (ref "Q8") (pin "3") (pinfunction "S_3") (pintype "bidirectional"))
      (node (ref "Q9") (pin "1") (pinfunction "S_1") (pintype "bidirectional"))
      (node (ref "Q9") (pin "2") (pinfunction "S_2") (pintype "bidirectional"))
      (node (ref "Q9") (pin "3") (pinfunction "S_3") (pintype "bidirectional"))
      (node (ref "R11") (pin "1") (pinfunction "1_1") (pintype "passive"))
      (node (ref "R19") (pin "1") (pinfunction "1_1") (pintype "passive"))
      (node (ref "R20") (pin "2") (pinfunction "2_2") (pintype "passive"))
      (node (ref "R23") (pin "1") (pinfunction "1_1") (pintype "passive"))
      (node (ref "R25") (pin "2") (pinfunction "2_2") (pintype "passive"))
      (node (ref "R26") (pin "2") (pinfunction "2_2") (pintype "passive"))
      (node (ref "R27") (pin "2") (pinfunction "2_2") (pintype "passive"))
      (node (ref "R29") (pin "2") (pinfunction "2_2") (pintype "passive"))
      (node (ref "R3") (pin "2") (pinfunction "2_2") (pintype "passive"))
      (node (ref "R30") (pin "2") (pinfunction "2_2") (pintype "passive"))
      (node (ref "R31") (pin "2") (pinfunction "2_2") (pintype "passive"))
      (node (ref "R32") (pin "2") (pinfunction "2_2") (pintype "passive"))
      (node (ref "R34") (pin "2") (pinfunction "2_2") (pintype "passive"))
      (node (ref "R35") (pin "2") (pinfunction "2_2") (pintype "passive"))
      (node (ref "R37") (pin "1") (pinfunction "1_1") (pintype "passive"))
      (node (ref "R4") (pin "2") (pinfunction "2_2") (pintype "passive"))
      (node (ref "R41") (pin "1") (pinfunction "1_1") (pintype "passive"))
      (node (ref "R42") (pin "2") (pinfunction "2_2") (pintype "passive"))
      (node (ref "R45") (pin "2") (pinfunction "2_2") (pintype "passive"))
      (node (ref "R49") (pin "1") (pinfunction "1_1") (pintype "passive"))
      (node (ref "R57") (pin "1") (pinfunction "1_1") (pintype "passive"))
      (node (ref "R58") (pin "2") (pinfunction "2_2") (pintype "passive"))
      (node (ref "R8") (pin "1") (pinfunction "1_1") (pintype "passive"))
      (node (ref "S1") (pin "3") (pinfunction "3_3") (pintype "passive"))
      (node (ref "S1") (pin "4") (pinfunction "4_4") (pintype "passive"))
      (node (ref "S2") (pin "3") (pinfunction "3_3") (pintype "passive"))
      (node (ref "S2") (pin "4") (pinfunction "4_4") (pintype "passive"))
      (node (ref "T1") (pin "1") (pinfunction "1_1") (pintype "bidirectional"))
      (node (ref "U1") (pin "6") (pinfunction "PGND_6") (pintype "bidirectional"))
      (node (ref "U10") (pin "6") (pinfunction "PGND_6") (pintype "bidirectional"))
      (node (ref "U11") (pin "2") (pinfunction "GND_2") (pintype "bidirectional"))
      (node (ref "U12") (pin "2") (pinfunction "VSS_2") (pintype "bidirectional"))
      (node (ref "U13") (pin "2") (pinfunction "A_2") (pintype "passive"))
      (node (ref "U2") (pin "2") (pinfunction "GND_2") (pintype "bidirectional"))
      (node (ref "U2") (pin "2@1") (pinfunction "GND_2@1") (pintype "bidirectional"))
      (node (ref "U3") (pin "2") (pinfunction "GND_2") (pintype "bidirectional"))
      (node (ref "U4") (pin "2") (pinfunction "GND_2") (pintype "bidirectional"))
      (node (ref "U5") (pin "2") (pinfunction "VSS_2") (pintype "bidirectional"))
      (node (ref "U6") (pin "2") (pinfunction "GND_2") (pintype "bidirectional"))
      (node (ref "U7") (pin "2") (pinfunction "VSS_2") (pintype "bidirectional"))
      (node (ref "U8") (pin "GND") (pinfunction "GND_GND") (pintype "bidirectional"))
      (node (ref "U8") (pin "GND2") (pinfunction "GND2_GND2") (pintype "bidirectional"))
      (node (ref "U8") (pin "GND4") (pinfunction "GND4_GND4") (pintype "bidirectional"))
      (node (ref "U9") (pin "3") (pinfunction "A_3") (pintype "passive"))
    )
    (net (code "33") (name "HSTH") (class "Default")
      (node (ref "C27") (pin "1") (pinfunction "1_1") (pintype "passive"))
      (node (ref "R44") (pin "1") (pinfunction "1_1") (pintype "passive"))
      (node (ref "T1") (pin "2") (pinfunction "2_2") (pintype "bidirectional"))
      (node (ref "U6") (pin "1") (pinfunction "2_1") (pintype "bidirectional"))
    )
    (net (code "34") (name "ISNS_REF") (class "Default")
      (node (ref "C26") (pin "1") (pinfunction "1_1") (pintype "passive"))
      (node (ref "C33") (pin "1") (pinfunction "1_1") (pintype "passive"))
      (node (ref "C5") (pin "1") (pinfunction "1_1") (pintype "passive"))
      (node (ref "R2") (pin "2") (pinfunction "2_2") (pintype "passive"))
      (node (ref "R3") (pin "1") (pinfunction "1_1") (pintype "passive"))
      (node (ref "TP5") (pin "1") (pinfunction "1_1") (pintype "bidirectional"))
      (node (ref "TP7") (pin "1") (pinfunction "1_1") (pintype "bidirectional"))
      (node (ref "U11") (pin "1") (pinfunction "REF_1") (pintype "bidirectional"))
      (node (ref "U3") (pin "1") (pinfunction "REF_1") (pintype "bidirectional"))
      (node (ref "U8") (pin "A5") (pinfunction "A5_A5") (pintype "bidirectional"))
    )
    (net (code "35") (name "NGATE1") (class "Default")
      (node (ref "Q3") (pin "4") (pinfunction "G_4") (pintype "bidirectional"))
      (node (ref "R4") (pin "1") (pinfunction "1_1") (pintype "passive"))
      (node (ref "U1") (pin "5") (pinfunction "DRVL_5") (pintype "bidirectional"))
    )
    (net (code "36") (name "NGATE2") (class "Default")
      (node (ref "Q8") (pin "4") (pinfunction "G_4") (pintype "bidirectional"))
      (node (ref "R45") (pin "1") (pinfunction "1_1") (pintype "passive"))
      (node (ref "U10") (pin "5") (pinfunction "DRVL_5") (pintype "bidirectional"))
    )
    (net (code "37") (name "Net-(C24-Pad1)") (class "Default")
      (node (ref "C24") (pin "1") (pinfunction "1_1") (pintype "passive"))
      (node (ref "R39") (pin "2") (pinfunction "2_2") (pintype "passive"))
    )
    (net (code "38") (name "Net-(D1-CATHODE)") (class "Default")
      (node (ref "C2") (pin "1") (pinfunction "1_1") (pintype "passive"))
      (node (ref "D1") (pin "K") (pinfunction "CATHODE_K") (pintype "passive"))
      (node (ref "U1") (pin "1") (pinfunction "BST_1") (pintype "bidirectional"))
    )
    (net (code "39") (name "Net-(D3-CATHODE)") (class "Default")
      (node (ref "C30") (pin "1") (pinfunction "1_1") (pintype "passive"))
      (node (ref "D3") (pin "K") (pinfunction "CATHODE_K") (pintype "passive"))
      (node (ref "U10") (pin "1") (pinfunction "BST_1") (pintype "bidirectional"))
    )
    (net (code "40") (name "Net-(F1-1)") (class "Default")
      (node (ref "F1") (pin "A") (pinfunction "1_A") (pintype "bidirectional"))
      (node (ref "Q4") (pin "5") (pinfunction "D_5") (pintype "bidirectional"))
      (node (ref "Q4") (pin "6") (pinfunction "D_6") (pintype "bidirectional"))
      (node (ref "Q4") (pin "7") (pinfunction "D_7") (pintype "bidirectional"))
      (node (ref "Q4") (pin "8") (pinfunction "D_8") (pintype "bidirectional"))
    )
    (net (code "41") (name "Net-(F2-1)") (class "Default")
      (node (ref "F2") (pin "A") (pinfunction "1_A") (pintype "bidirectional"))
      (node (ref "Q5") (pin "2") (pinfunction "D_2") (pintype "bidirectional"))
    )
    (net (code "42") (name "Net-(F3-1)") (class "Default")
      (node (ref "F3") (pin "A") (pinfunction "1_A") (pintype "bidirectional"))
      (node (ref "Q9") (pin "5") (pinfunction "D_5") (pintype "bidirectional"))
      (node (ref "Q9") (pin "6") (pinfunction "D_6") (pintype "bidirectional"))
      (node (ref "Q9") (pin "7") (pinfunction "D_7") (pintype "bidirectional"))
      (node (ref "Q9") (pin "8") (pinfunction "D_8") (pintype "bidirectional"))
    )
    (net (code "43") (name "Net-(J1-Pad2)") (class "Default")
      (node (ref "J1") (pin "2") (pinfunction "2_2") (pintype "passive"))
      (node (ref "R6") (pin "1") (pinfunction "1_1") (pintype "passive"))
    )
    (net (code "44") (name "Net-(L2-P$1)") (class "Default")
      (node (ref "C13") (pin "2") (pinfunction "2_2") (pintype "passive"))
      (node (ref "L2") (pin "1") (pinfunction "P$1_1") (pintype "passive"))
      (node (ref "U4") (pin "6") (pinfunction "SW_6") (pintype "bidirectional"))
    )
    (net (code "45") (name "Net-(LED1-DIN)") (class "Default")
      (node (ref "LED1") (pin "4-DIN") (pinfunction "DIN_4-DIN") (pintype "input"))
      (node (ref "Q1") (pin "3") (pinfunction "D_3") (pintype "bidirectional"))
      (node (ref "R1") (pin "2") (pinfunction "2_2") (pintype "passive"))
    )
    (net (code "46") (name "Net-(LED2-DOUT)") (class "Default")
      (node (ref "JP3") (pin "1") (pinfunction "1_1") (pintype "passive"))
      (node (ref "LED2") (pin "2-DOUT") (pinfunction "DOUT_2-DOUT") (pintype "output"))
    )
    (net (code "47") (name "Net-(Q5-G)") (class "Default")
      (node (ref "Q5") (pin "1") (pinfunction "G_1") (pintype "bidirectional"))
      (node (ref "R40") (pin "1") (pinfunction "1_1") (pintype "passive"))
    )
    (net (code "48") (name "Net-(Q6-D)") (class "Default")
      (node (ref "J3") (pin "2") (pinfunction "2_2") (pintype "passive"))
      (node (ref "Q6") (pin "3") (pinfunction "D_3") (pintype "bidirectional"))
    )
    (net (code "49") (name "Net-(U3-IN-)") (class "Default")
      (node (ref "C10") (pin "1") (pinfunction "1_1") (pintype "passive"))
      (node (ref "C9") (pin "+") (pinfunction "+_+") (pintype "passive"))
      (node (ref "L1") (pin "P$2") (pinfunction "P$2_P$2") (pintype "passive"))
      (node (ref "R12") (pin "1") (pinfunction "1_1") (pintype "passive"))
      (node (ref "U3") (pin "5") (pinfunction "IN-_5") (pintype "bidirectional"))
    )
    (net (code "50") (name "Net-(U3-OUT)") (class "Default")
      (node (ref "R9") (pin "1") (pinfunction "1_1") (pintype "passive"))
      (node (ref "U3") (pin "6") (pinfunction "OUT_6") (pintype "bidirectional"))
    )
    (net (code "51") (name "Net-(U4-BST)") (class "Default")
      (node (ref "C13") (pin "1") (pinfunction "1_1") (pintype "passive"))
      (node (ref "U4") (pin "1") (pinfunction "BST_1") (pintype "bidirectional"))
    )
    (net (code "52") (name "Net-(U4-EN)") (class "Default")
      (node (ref "R21") (pin "1") (pinfunction "1_1") (pintype "passive"))
      (node (ref "U4") (pin "4") (pinfunction "EN_4") (pintype "bidirectional"))
    )
    (net (code "53") (name "Net-(U4-FB)") (class "Default")
      (node (ref "R22") (pin "1") (pinfunction "1_1") (pintype "passive"))
      (node (ref "R23") (pin "2") (pinfunction "2_2") (pintype "passive"))
      (node (ref "U4") (pin "3") (pinfunction "FB_3") (pintype "bidirectional"))
    )
    (net (code "54") (name "Net-(U5-VIN+)") (class "Default")
      (node (ref "R15") (pin "2") (pinfunction "2_2") (pintype "passive"))
      (node (ref "R19") (pin "2") (pinfunction "2_2") (pintype "passive"))
      (node (ref "U5") (pin "1") (pinfunction "VIN+_1") (pintype "bidirectional"))
    )
    (net (code "55") (name "Net-(U5-VIN-)") (class "Default")
      (node (ref "R14") (pin "2") (pinfunction "2_2") (pintype "passive"))
      (node (ref "R18") (pin "1") (pinfunction "1_1") (pintype "passive"))
      (node (ref "U5") (pin "3") (pinfunction "VIN-_3") (pintype "bidirectional"))
    )
    (net (code "56") (name "Net-(U5-VOUT)") (class "Default")
      (node (ref "R18") (pin "2") (pinfunction "2_2") (pintype "passive"))
      (node (ref "R24") (pin "1") (pinfunction "1_1") (pintype "passive"))
      (node (ref "U5") (pin "4") (pinfunction "VOUT_4") (pintype "bidirectional"))
    )
    (net (code "57") (name "Net-(U7-VIN+)") (class "Default")
      (node (ref "R28") (pin "2") (pinfunction "2_2") (pintype "passive"))
      (node (ref "R29") (pin "1") (pinfunction "1_1") (pintype "passive"))
      (node (ref "U7") (pin "1") (pinfunction "VIN+_1") (pintype "bidirectional"))
    )
    (net (code "58") (name "Net-(U7-VIN-)") (class "Default")
      (node (ref "C19") (pin "1") (pinfunction "1_1") (pintype "passive"))
      (node (ref "R36") (pin "2") (pinfunction "2_2") (pintype "passive"))
      (node (ref "R37") (pin "2") (pinfunction "2_2") (pintype "passive"))
      (node (ref "R39") (pin "1") (pinfunction "1_1") (pintype "passive"))
      (node (ref "U7") (pin "3") (pinfunction "VIN-_3") (pintype "bidirectional"))
    )
    (net (code "59") (name "Net-(U8-A12{slash}D+)") (class "Default")
      (node (ref "R38") (pin "2") (pinfunction "2_2") (pintype "passive"))
      (node (ref "U8") (pin "A12") (pinfunction "A12/D+_A12") (pintype "bidirectional"))
    )
    (net (code "60") (name "Net-(U11-IN-)") (class "Default")
      (node (ref "C35") (pin "+") (pinfunction "+_+") (pintype "passive"))
      (node (ref "C36") (pin "1") (pinfunction "1_1") (pintype "passive"))
      (node (ref "L3") (pin "P$2") (pinfunction "P$2_P$2") (pintype "passive"))
      (node (ref "R50") (pin "1") (pinfunction "1_1") (pintype "passive"))
      (node (ref "U11") (pin "5") (pinfunction "IN-_5") (pintype "bidirectional"))
    )
    (net (code "61") (name "Net-(U11-OUT)") (class "Default")
      (node (ref "R47") (pin "1") (pinfunction "1_1") (pintype "passive"))
      (node (ref "U11") (pin "6") (pinfunction "OUT_6") (pintype "bidirectional"))
    )
    (net (code "62") (name "Net-(U12-VIN+)") (class "Default")
      (node (ref "R53") (pin "2") (pinfunction "2_2") (pintype "passive"))
      (node (ref "R57") (pin "2") (pinfunction "2_2") (pintype "passive"))
      (node (ref "U12") (pin "1") (pinfunction "VIN+_1") (pintype "bidirectional"))
    )
    (net (code "63") (name "Net-(U12-VIN-)") (class "Default")
      (node (ref "R52") (pin "2") (pinfunction "2_2") (pintype "passive"))
      (node (ref "R56") (pin "1") (pinfunction "1_1") (pintype "passive"))
      (node (ref "U12") (pin "3") (pinfunction "VIN-_3") (pintype "bidirectional"))
    )
    (net (code "64") (name "Net-(U12-VOUT)") (class "Default")
      (node (ref "R56") (pin "2") (pinfunction "2_2") (pintype "passive"))
      (node (ref "R59") (pin "1") (pinfunction "1_1") (pintype "passive"))
      (node (ref "U12") (pin "4") (pinfunction "VOUT_4") (pintype "bidirectional"))
    )
    (net (code "65") (name "OA1+") (class "Default")
      (node (ref "J2") (pin "2") (pinfunction "2_2") (pintype "passive"))
      (node (ref "R15") (pin "1") (pinfunction "1_1") (pintype "passive"))
      (node (ref "R17") (pin "1") (pinfunction "1_1") (pintype "passive"))
    )
    (net (code "66") (name "OA1-") (class "Default")
      (node (ref "J2") (pin "1") (pinfunction "1_1") (pintype "passive"))
      (node (ref "R13") (pin "1") (pinfunction "1_1") (pintype "passive"))
      (node (ref "R14") (pin "1") (pinfunction "1_1") (pintype "passive"))
    )
    (net (code "67") (name "OA2+") (class "Default")
      (node (ref "J4") (pin "2") (pinfunction "2_2") (pintype "passive"))
      (node (ref "R53") (pin "1") (pinfunction "1_1") (pintype "passive"))
      (node (ref "R55") (pin "1") (pinfunction "1_1") (pintype "passive"))
    )
    (net (code "68") (name "OA2-") (class "Default")
      (node (ref "J4") (pin "1") (pinfunction "1_1") (pintype "passive"))
      (node (ref "R51") (pin "1") (pinfunction "1_1") (pintype "passive"))
      (node (ref "R52") (pin "1") (pinfunction "1_1") (pintype "passive"))
    )
    (net (code "69") (name "PB5") (class "Default")
      (node (ref "JP1") (pin "3") (pinfunction "3_3") (pintype "passive"))
      (node (ref "R35") (pin "1") (pinfunction "1_1") (pintype "passive"))
      (node (ref "U8") (pin "B5") (pinfunction "B5_B5") (pintype "bidirectional"))
    )
    (net (code "70") (name "PB12") (class "Default")
      (node (ref "R34") (pin "1") (pinfunction "1_1") (pintype "passive"))
      (node (ref "U6") (pin "6") (pinfunction "SEL_6") (pintype "bidirectional"))
      (node (ref "U8") (pin "B12") (pinfunction "B12_B12") (pintype "bidirectional"))
    )
    (net (code "71") (name "PGATE1") (class "Default")
      (node (ref "Q2") (pin "4") (pinfunction "G_4") (pintype "bidirectional"))
      (node (ref "R5") (pin "2") (pinfunction "2_2") (pintype "passive"))
      (node (ref "U1") (pin "8") (pinfunction "DRVH_8") (pintype "bidirectional"))
    )
    (net (code "72") (name "PGATE2") (class "Default")
      (node (ref "Q7") (pin "4") (pinfunction "G_4") (pintype "bidirectional"))
      (node (ref "R46") (pin "1") (pinfunction "1_1") (pintype "passive"))
      (node (ref "U10") (pin "8") (pinfunction "DRVH_8") (pintype "bidirectional"))
    )
    (net (code "73") (name "S1") (class "Default")
      (node (ref "S1") (pin "1") (pinfunction "1_1") (pintype "passive"))
      (node (ref "S1") (pin "2") (pinfunction "2_2") (pintype "passive"))
      (node (ref "U8") (pin "B9") (pinfunction "B9_B9") (pintype "bidirectional"))
    )
    (net (code "74") (name "S2") (class "Default")
      (node (ref "S2") (pin "1") (pinfunction "1_1") (pintype "passive"))
      (node (ref "S2") (pin "2") (pinfunction "2_2") (pintype "passive"))
      (node (ref "U8") (pin "C13") (pinfunction "C13_C13") (pintype "bidirectional"))
    )
    (net (code "75") (name "SCL-TX") (class "Default")
      (node (ref "JP2") (pin "2") (pinfunction "2_2") (pintype "passive"))
      (node (ref "U8") (pin "B10") (pinfunction "B10_B10") (pintype "bidirectional"))
    )
    (net (code "76") (name "SDA-RX") (class "Default")
      (node (ref "JP2") (pin "3") (pinfunction "3_3") (pintype "passive"))
      (node (ref "U8") (pin "B11") (pinfunction "B11_B11") (pintype "bidirectional"))
    )
    (net (code "77") (name "unconnected-(U8-PadA15)") (class "Default")
      (node (ref "U8") (pin "A15") (pinfunction "A15_A15") (pintype "bidirectional"))
    )
    (net (code "78") (name "unconnected-(U8-PadB6)") (class "Default")
      (node (ref "U8") (pin "B6") (pinfunction "B6_B6") (pintype "bidirectional"))
    )
    (net (code "79") (name "unconnected-(U8-PadB7)") (class "Default")
      (node (ref "U8") (pin "B7") (pinfunction "B7_B7") (pintype "bidirectional"))
    )
    (net (code "80") (name "unconnected-(U8-PadB15)") (class "Default")
      (node (ref "U8") (pin "B15") (pinfunction "B15_B15") (pintype "bidirectional"))
    )
    (net (code "81") (name "unconnected-(U8-PadRST)") (class "Default")
      (node (ref "U8") (pin "RST") (pinfunction "RST_RST") (pintype "bidirectional"))
    )
    (net (code "82") (name "unconnected-(U8-VB-PadVBAT)") (class "Default")
      (node (ref "U8") (pin "VBAT") (pinfunction "VB_VBAT") (pintype "bidirectional"))
    )
  )
)
